# InvertingOpAmp.net
KiCad netlist of a schematic drawn in Altium Designer
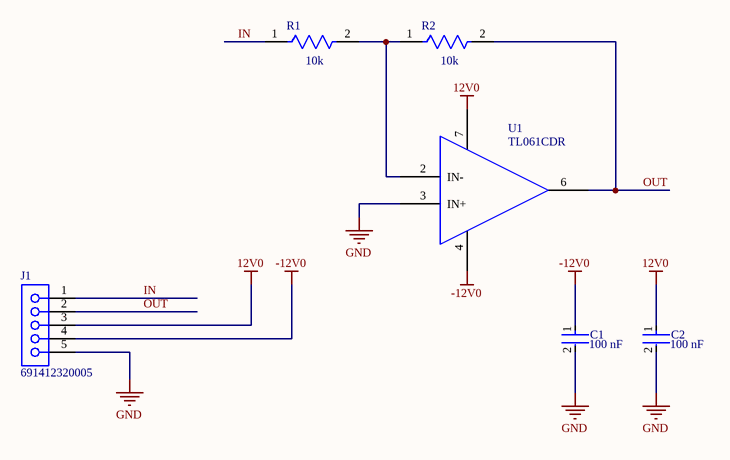
[diagram p0: InvertingOpAmp.SchDoc]

(export (version "E")
  (design (tool "Eeschema 10.0.6"))
  (components
    (comp (ref "C1")
      (value "CC0805KRX7R9BB104")
      (footprint "FP-CC0805-0_85-MFG")
      (description "CAP CER 0.1UF 50V X7R 0805")
      (fields
        (field (name "TOLERANCE") "0.1")
        (field (name "CAPACITANCE") "100 nF")
        (field (name "MANUFACTURER") "Yageo")
      )
      (libsource (lib "Altium Content Vault") (part "11868f565c42a9108669ba33697ecf6"))
    )
    (comp (ref "C2")
      (value "CC0805KRX7R9BB104")
      (footprint "FP-CC0805-0_85-MFG")
      (description "CAP CER 0.1UF 50V X7R 0805")
      (fields
        (field (name "TOLERANCE") "0.1")
        (field (name "CAPACITANCE") "100 nF")
        (field (name "MANUFACTURER") "Yageo")
      )
      (libsource (lib "Altium Content Vault") (part "11868f565c42a9108669ba33697ecf6"))
    )
    (comp (ref "J1")
      (value "691412320005")
      (footprint "691412320005")
      (libsource (lib "Altium Content Vault") (part "TBL - 1R - 05P - Female"))
    )
    (comp (ref "R1")
      (value "RR1220P-103-D")
      (footprint "FP-RR1220-IPC_A")
      (description "10kΩ ±0.5% 0.1W 1/10W Chip Resistor 0805 (2012 Metric) Thin Film")
      (fields (field (name "RESISTANCE") "10k") (field (name "TOLERANCE") "0.5%"))
      (libsource (lib "Altium Content Vault") (part "1029c3af85768c4190bb7ad29bc67b5"))
    )
    (comp (ref "R2")
      (value "RR1220P-103-D")
      (footprint "FP-RR1220-IPC_A")
      (description "10kΩ ±0.5% 0.1W 1/10W Chip Resistor 0805 (2012 Metric) Thin Film")
      (fields (field (name "RESISTANCE") "10k") (field (name "TOLERANCE") "0.5%"))
      (libsource (lib "Altium Content Vault") (part "1029c3af85768c4190bb7ad29bc67b5"))
    )
    (comp (ref "U1")
      (value "TL061CDR")
      (footprint "SOIC8")
      (description "IC OPAMP JFET 1 CIRCUIT 8SOIC")
      (libsource (lib "ECEN403Parts") (part "TLO61"))
    )
  )
  (nets
    (net (code "1") (name "-12V0") (class "Default")
      (node (ref "C1") (pin "1") (pinfunction "1_1") (pintype "passive"))
      (node (ref "J1") (pin "4") (pinfunction "4_4") (pintype "passive"))
      (node (ref "U1") (pin "4") (pinfunction "VCC-_4") (pintype "passive"))
    )
    (net (code "2") (name "/IN") (class "Default")
      (node (ref "J1") (pin "1") (pinfunction "1_1") (pintype "passive"))
      (node (ref "R1") (pin "1") (pinfunction "1_1") (pintype "passive"))
    )
    (net (code "3") (name "/OUT") (class "Default")
      (node (ref "J1") (pin "2") (pinfunction "2_2") (pintype "passive"))
      (node (ref "R2") (pin "2") (pinfunction "2_2") (pintype "passive"))
      (node (ref "U1") (pin "6") (pinfunction "OUT_6") (pintype "passive"))
    )
    (net (code "4") (name "12V0") (class "Default")
      (node (ref "C2") (pin "1") (pinfunction "1_1") (pintype "passive"))
      (node (ref "J1") (pin "3") (pinfunction "3_3") (pintype "passive"))
      (node (ref "U1") (pin "7") (pinfunction "VCC+_7") (pintype "passive"))
    )
    (net (code "5") (name "GND") (class "Default")
      (node (ref "C1") (pin "2") (pinfunction "2_2") (pintype "passive"))
      (node (ref "C2") (pin "2") (pinfunction "2_2") (pintype "passive"))
      (node (ref "J1") (pin "5") (pinfunction "5_5") (pintype "passive"))
      (node (ref "U1") (pin "3") (pinfunction "IN+_3") (pintype "passive"))
    )
    (net (code "6") (name "Net-(U1-IN-)") (class "Default")
      (node (ref "R1") (pin "2") (pinfunction "2_2") (pintype "passive"))
      (node (ref "R2") (pin "1") (pinfunction "1_1") (pintype "passive"))
      (node (ref "U1") (pin "2") (pinfunction "IN-_2") (pintype "passive"))
    )
  )
)
